# Sheet1.net
KiCad netlist of a schematic drawn in Altium Designer
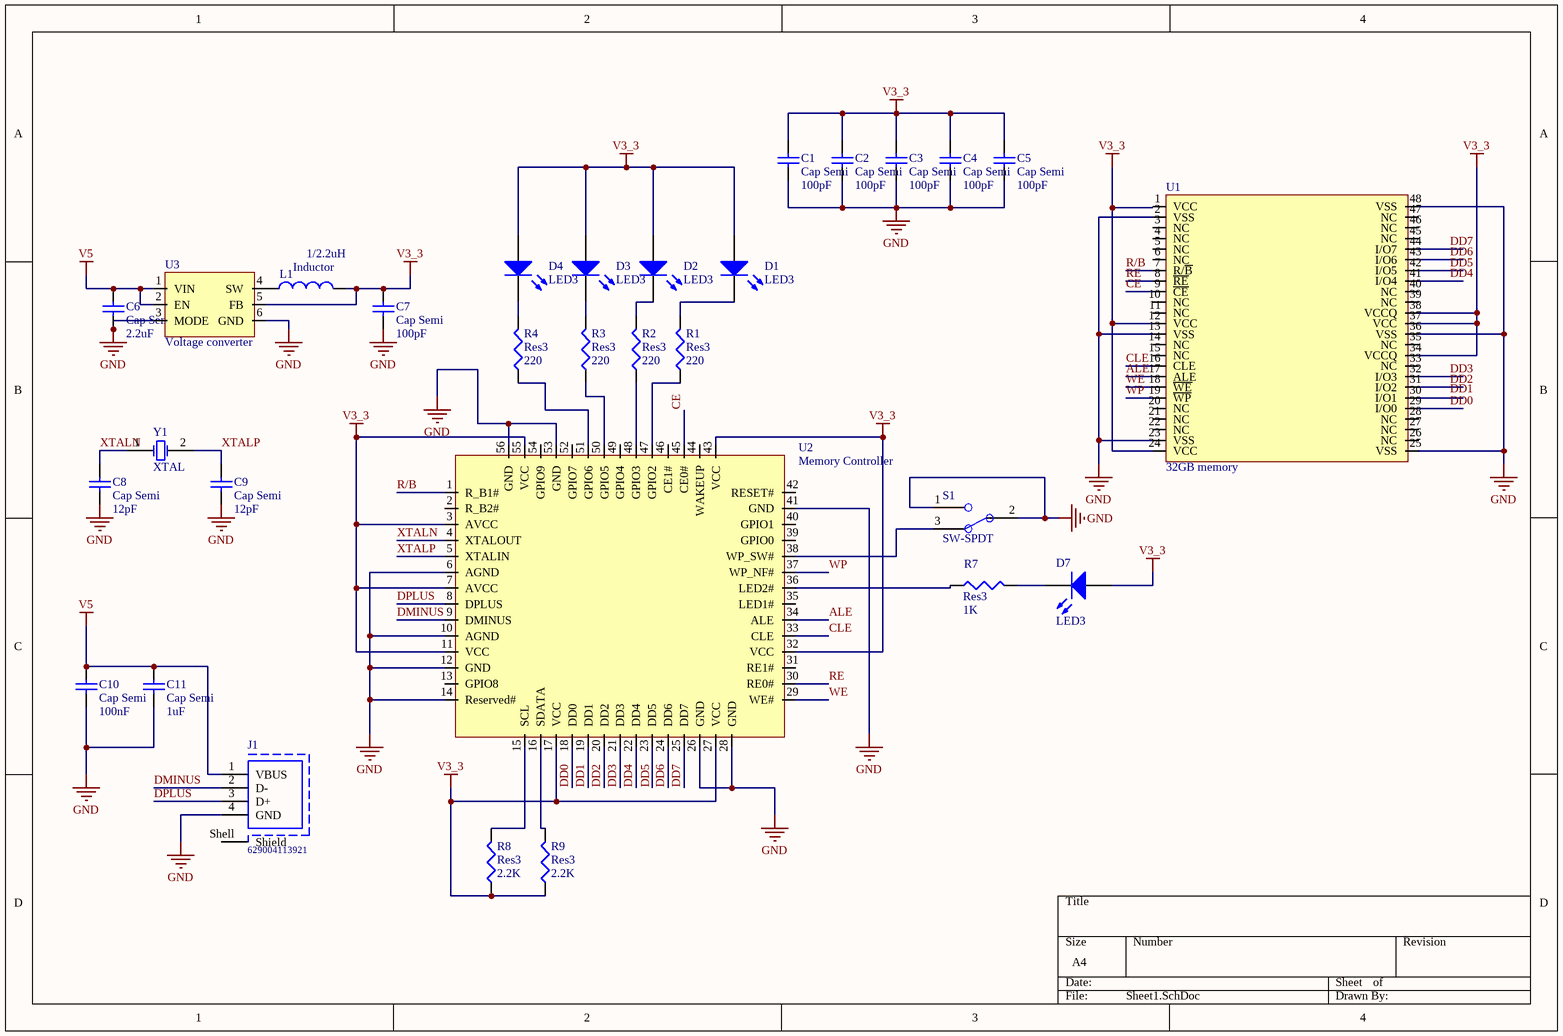
[diagram p0: Sheet1.SchDoc]

(export (version "E")
  (design (tool "Eeschema 10.0.6"))
  (components
    (comp (ref "C1")
      (value "Cap Semi")
      (footprint "CAPC3216L")
      (description "Capacitor (Semiconductor SIM Model)")
      (fields (field (name "ALTIUM_VALUE") "100pF") (field (name "PUBLISHER") "Altium Limited"))
      (libsource (lib "Miscellaneous Devices") (part "Cap Semi"))
    )
    (comp (ref "C2")
      (value "Cap Semi")
      (footprint "CAPC3216L")
      (description "Capacitor (Semiconductor SIM Model)")
      (fields (field (name "ALTIUM_VALUE") "100pF") (field (name "PUBLISHER") "Altium Limited"))
      (libsource (lib "Miscellaneous Devices") (part "Cap Semi"))
    )
    (comp (ref "C3")
      (value "Cap Semi")
      (footprint "CAPC3216L")
      (description "Capacitor (Semiconductor SIM Model)")
      (fields (field (name "ALTIUM_VALUE") "100pF") (field (name "PUBLISHER") "Altium Limited"))
      (libsource (lib "Miscellaneous Devices") (part "Cap Semi"))
    )
    (comp (ref "C4")
      (value "Cap Semi")
      (footprint "CAPC3216L")
      (description "Capacitor (Semiconductor SIM Model)")
      (fields (field (name "ALTIUM_VALUE") "100pF") (field (name "PUBLISHER") "Altium Limited"))
      (libsource (lib "Miscellaneous Devices") (part "Cap Semi"))
    )
    (comp (ref "C5")
      (value "Cap Semi")
      (footprint "CAPC3216L")
      (description "Capacitor (Semiconductor SIM Model)")
      (fields (field (name "ALTIUM_VALUE") "100pF") (field (name "PUBLISHER") "Altium Limited"))
      (libsource (lib "Miscellaneous Devices") (part "Cap Semi"))
    )
    (comp (ref "C6")
      (value "Cap Semi")
      (footprint "CAPC3216L")
      (description "Capacitor (Semiconductor SIM Model)")
      (fields (field (name "ALTIUM_VALUE") "2.2uF") (field (name "PUBLISHER") "Altium Limited"))
      (libsource (lib "Miscellaneous Devices") (part "Cap Semi"))
    )
    (comp (ref "C7")
      (value "Cap Semi")
      (footprint "CAPC3216L")
      (description "Capacitor (Semiconductor SIM Model)")
      (fields (field (name "ALTIUM_VALUE") "100pF") (field (name "PUBLISHER") "Altium Limited"))
      (libsource (lib "Miscellaneous Devices") (part "Cap Semi"))
    )
    (comp (ref "C8")
      (value "Cap Semi")
      (footprint "CAPC3216L")
      (description "Capacitor (Semiconductor SIM Model)")
      (fields (field (name "ALTIUM_VALUE") "12pF") (field (name "PUBLISHER") "Altium Limited"))
      (libsource (lib "Miscellaneous Devices") (part "Cap Semi"))
    )
    (comp (ref "C9")
      (value "Cap Semi")
      (footprint "CAPC3216L")
      (description "Capacitor (Semiconductor SIM Model)")
      (fields (field (name "ALTIUM_VALUE") "12pF") (field (name "PUBLISHER") "Altium Limited"))
      (libsource (lib "Miscellaneous Devices") (part "Cap Semi"))
    )
    (comp (ref "C10")
      (value "Cap Semi")
      (footprint "CAPC3216L")
      (description "Capacitor (Semiconductor SIM Model)")
      (fields (field (name "ALTIUM_VALUE") "100nF") (field (name "PUBLISHER") "Altium Limited"))
      (libsource (lib "Miscellaneous Devices") (part "Cap Semi"))
    )
    (comp (ref "C11")
      (value "Cap Semi")
      (footprint "CAPC3216L")
      (description "Capacitor (Semiconductor SIM Model)")
      (fields (field (name "ALTIUM_VALUE") "1uF") (field (name "PUBLISHER") "Altium Limited"))
      (libsource (lib "Miscellaneous Devices") (part "Cap Semi"))
    )
    (comp (ref "D1")
      (value "LED3")
      (footprint "DSO-C2/D5.6")
      (description "Typical BLUE SiC LED")
      (fields (field (name "PUBLISHER") "Altium Limited"))
      (libsource (lib "Miscellaneous Devices") (part "LED3"))
    )
    (comp (ref "D2")
      (value "LED3")
      (footprint "DSO-C2/D5.6")
      (description "Typical BLUE SiC LED")
      (fields (field (name "PUBLISHER") "Altium Limited"))
      (libsource (lib "Miscellaneous Devices") (part "LED3"))
    )
    (comp (ref "D3")
      (value "LED3")
      (footprint "DSO-C2/D5.6")
      (description "Typical BLUE SiC LED")
      (fields (field (name "PUBLISHER") "Altium Limited"))
      (libsource (lib "Miscellaneous Devices") (part "LED3"))
    )
    (comp (ref "D4")
      (value "LED3")
      (footprint "DSO-C2/D5.6")
      (description "Typical BLUE SiC LED")
      (fields (field (name "PUBLISHER") "Altium Limited"))
      (libsource (lib "Miscellaneous Devices") (part "LED3"))
    )
    (comp (ref "D7")
      (value "LED3")
      (footprint "DSO-C2/D5.6")
      (description "Typical BLUE SiC LED")
      (fields (field (name "PUBLISHER") "Altium Limited"))
      (libsource (lib "Miscellaneous Devices") (part "LED3"))
    )
    (comp (ref "J1")
      (value "629004113921")
      (footprint "629004113921")
      (description "USB 2.0 Type A Plug WR-COM, Horizontal, SMT, with Clips")
      (fields (field (name "PUBLISHER") "Wurth Elektronik"))
      (libsource (lib "Altium_WR-COM_USB-Connectors (rev19a)") (part "629004113921"))
    )
    (comp (ref "L1")
      (value "Inductor")
      (footprint "INDC1005AL")
      (fields (field (name "ALTIUM_VALUE") "1/2.2uH") (field (name "PUBLISHER") "Altium Limited"))
      (libsource (lib "Miscellaneous Devices") (part "Inductor"))
    )
    (comp (ref "R1")
      (value "Res3")
      (footprint "RESC1608L")
      (description "Resistor")
      (fields (field (name "ALTIUM_VALUE") "220") (field (name "PUBLISHER") "Altium Limited"))
      (libsource (lib "Miscellaneous Devices") (part "Res3"))
    )
    (comp (ref "R2")
      (value "Res3")
      (footprint "RESC1608L")
      (description "Resistor")
      (fields (field (name "ALTIUM_VALUE") "220") (field (name "PUBLISHER") "Altium Limited"))
      (libsource (lib "Miscellaneous Devices") (part "Res3"))
    )
    (comp (ref "R3")
      (value "Res3")
      (footprint "RESC1608L")
      (description "Resistor")
      (fields (field (name "ALTIUM_VALUE") "220") (field (name "PUBLISHER") "Altium Limited"))
      (libsource (lib "Miscellaneous Devices") (part "Res3"))
    )
    (comp (ref "R4")
      (value "Res3")
      (footprint "RESC1608L")
      (description "Resistor")
      (fields (field (name "ALTIUM_VALUE") "220") (field (name "PUBLISHER") "Altium Limited"))
      (libsource (lib "Miscellaneous Devices") (part "Res3"))
    )
    (comp (ref "R7")
      (value "Res3")
      (footprint "RESC1608L")
      (description "Resistor")
      (fields (field (name "ALTIUM_VALUE") "1K") (field (name "PUBLISHER") "Altium Limited"))
      (libsource (lib "Miscellaneous Devices") (part "Res3"))
    )
    (comp (ref "R8")
      (value "Res3")
      (footprint "RESC1608L")
      (description "Resistor")
      (fields (field (name "ALTIUM_VALUE") "2.2K") (field (name "PUBLISHER") "Altium Limited"))
      (libsource (lib "Miscellaneous Devices") (part "Res3"))
    )
    (comp (ref "R9")
      (value "Res3")
      (footprint "RESC1608L")
      (description "Resistor")
      (fields (field (name "ALTIUM_VALUE") "2.2K") (field (name "PUBLISHER") "Altium Limited"))
      (libsource (lib "Miscellaneous Devices") (part "Res3"))
    )
    (comp (ref "S1")
      (value "SW-SPDT")
      (footprint "SW-SPDT")
      (libsource (lib "Integrated_Library1") (part "Component_4"))
    )
    (comp (ref "U1")
      (value "32GB memory")
      (footprint "TSSOP50P2000X120-48N")
      (libsource (lib "Integrated_Library1") (part "Component_2"))
    )
    (comp (ref "U2")
      (value "Memory Controller")
      (footprint "QFN50P800X800X100-56N")
      (libsource (lib "Integrated_Library1") (part "Component_1"))
    )
    (comp (ref "U3")
      (value "Voltage converter")
      (footprint "USON")
      (libsource (lib "Integrated_Library1") (part "Component_3"))
    )
    (comp (ref "Y1")
      (value "XTAL")
      (footprint "BCY-W2/D3.1")
      (description "Crystal Oscillator")
      (fields (field (name "PUBLISHER") "Altium Limited"))
      (libsource (lib "Miscellaneous Devices") (part "XTAL"))
    )
  )
  (nets
    (net (code "1") (name "/ALE") (class "Default")
      (node (ref "U1") (pin "17") (pinfunction "ALE_17") (pintype "passive"))
      (node (ref "U2") (pin "34") (pinfunction "ALE_34") (pintype "passive"))
    )
    (net (code "2") (name "/CE") (class "Default")
      (node (ref "U1") (pin "9") (pinfunction "~{CE}_9") (pintype "passive"))
      (node (ref "U2") (pin "45") (pinfunction "CE0#_45") (pintype "passive"))
    )
    (net (code "3") (name "/CLE") (class "Default")
      (node (ref "U1") (pin "16") (pinfunction "CLE_16") (pintype "passive"))
      (node (ref "U2") (pin "33") (pinfunction "CLE_33") (pintype "passive"))
    )
    (net (code "4") (name "/DD0") (class "Default")
      (node (ref "U1") (pin "29") (pinfunction "I/O0_29") (pintype "passive"))
      (node (ref "U2") (pin "18") (pinfunction "DD0_18") (pintype "passive"))
    )
    (net (code "5") (name "/DD1") (class "Default")
      (node (ref "U2") (pin "19") (pinfunction "DD1_19") (pintype "passive"))
    )
    (net (code "6") (name "/DD2") (class "Default")
      (node (ref "U1") (pin "31") (pinfunction "I/O2_31") (pintype "passive"))
      (node (ref "U2") (pin "20") (pinfunction "DD2_20") (pintype "passive"))
    )
    (net (code "7") (name "/DD3") (class "Default")
      (node (ref "U1") (pin "32") (pinfunction "I/O3_32") (pintype "passive"))
      (node (ref "U2") (pin "21") (pinfunction "DD3_21") (pintype "passive"))
    )
    (net (code "8") (name "/DD4") (class "Default")
      (node (ref "U1") (pin "41") (pinfunction "I/O4_41") (pintype "passive"))
      (node (ref "U2") (pin "22") (pinfunction "DD4_22") (pintype "passive"))
    )
    (net (code "9") (name "/DD5") (class "Default")
      (node (ref "U1") (pin "42") (pinfunction "I/O5_42") (pintype "passive"))
    )
    (net (code "10") (name "/DD6") (class "Default")
      (node (ref "U1") (pin "43") (pinfunction "I/O6_43") (pintype "passive"))
      (node (ref "U2") (pin "24") (pinfunction "DD6_24") (pintype "passive"))
    )
    (net (code "11") (name "/DD7") (class "Default")
      (node (ref "U1") (pin "44") (pinfunction "I/O7_44") (pintype "passive"))
      (node (ref "U2") (pin "25") (pinfunction "DD7_25") (pintype "passive"))
    )
    (net (code "12") (name "/DMINUS") (class "Default")
      (node (ref "J1") (pin "2") (pinfunction "D-_2") (pintype "passive"))
      (node (ref "U2") (pin "9") (pinfunction "DMINUS_9") (pintype "passive"))
    )
    (net (code "13") (name "/DPLUS") (class "Default")
      (node (ref "J1") (pin "3") (pinfunction "D+_3") (pintype "passive"))
      (node (ref "U2") (pin "8") (pinfunction "DPLUS_8") (pintype "passive"))
    )
    (net (code "14") (name "/RE") (class "Default")
      (node (ref "U1") (pin "8") (pinfunction "~{RE}_8") (pintype "passive"))
      (node (ref "U2") (pin "30") (pinfunction "RE0#_30") (pintype "passive"))
    )
    (net (code "15") (name "/R{slash}B") (class "Default")
      (node (ref "U1") (pin "7") (pinfunction "R/~{B}_7") (pintype "passive"))
      (node (ref "U2") (pin "1") (pinfunction "R_B1#_1") (pintype "passive"))
    )
    (net (code "16") (name "/WE") (class "Default")
      (node (ref "U1") (pin "18") (pinfunction "~{WE}_18") (pintype "passive"))
      (node (ref "U2") (pin "29") (pinfunction "WE#_29") (pintype "passive"))
    )
    (net (code "17") (name "/WP") (class "Default")
      (node (ref "U1") (pin "19") (pinfunction "~{WP}_19") (pintype "passive"))
      (node (ref "U2") (pin "37") (pinfunction "WP_NF#_37") (pintype "passive"))
    )
    (net (code "18") (name "/XTALN") (class "Default")
      (node (ref "C8") (pin "2") (pinfunction "2_2") (pintype "passive"))
      (node (ref "U2") (pin "4") (pinfunction "XTALOUT_4") (pintype "passive"))
      (node (ref "Y1") (pin "1") (pinfunction "OSC1_1") (pintype "passive"))
    )
    (net (code "19") (name "/XTALP") (class "Default")
      (node (ref "C9") (pin "2") (pinfunction "2_2") (pintype "passive"))
      (node (ref "U2") (pin "5") (pinfunction "XTALIN_5") (pintype "passive"))
      (node (ref "Y1") (pin "2") (pinfunction "OSC2_2") (pintype "passive"))
    )
    (net (code "20") (name "GND") (class "Default")
      (node (ref "C1") (pin "1") (pinfunction "1_1") (pintype "passive"))
      (node (ref "C10") (pin "1") (pinfunction "1_1") (pintype "passive"))
      (node (ref "C11") (pin "1") (pinfunction "1_1") (pintype "passive"))
      (node (ref "C2") (pin "1") (pinfunction "1_1") (pintype "passive"))
      (node (ref "C3") (pin "1") (pinfunction "1_1") (pintype "passive"))
      (node (ref "C4") (pin "1") (pinfunction "1_1") (pintype "passive"))
      (node (ref "C5") (pin "1") (pinfunction "1_1") (pintype "passive"))
      (node (ref "C6") (pin "2") (pinfunction "2_2") (pintype "passive"))
      (node (ref "C7") (pin "1") (pinfunction "1_1") (pintype "passive"))
      (node (ref "C8") (pin "1") (pinfunction "1_1") (pintype "passive"))
      (node (ref "C9") (pin "1") (pinfunction "1_1") (pintype "passive"))
      (node (ref "J1") (pin "4") (pinfunction "GND_4") (pintype "passive"))
      (node (ref "S1") (pin "1") (pinfunction "1_1") (pintype "passive"))
      (node (ref "S1") (pin "2") (pinfunction "2_2") (pintype "passive"))
      (node (ref "U1") (pin "13") (pinfunction "VSS_13") (pintype "passive"))
      (node (ref "U1") (pin "2") (pinfunction "VSS_2") (pintype "passive"))
      (node (ref "U1") (pin "23") (pinfunction "VSS_23") (pintype "passive"))
      (node (ref "U1") (pin "25") (pinfunction "VSS_25") (pintype "passive"))
      (node (ref "U1") (pin "36") (pinfunction "VSS_36") (pintype "passive"))
      (node (ref "U1") (pin "48") (pinfunction "VSS_48") (pintype "passive"))
      (node (ref "U2") (pin "10") (pinfunction "AGND_10") (pintype "passive"))
      (node (ref "U2") (pin "12") (pinfunction "GND_12") (pintype "passive"))
      (node (ref "U2") (pin "14") (pinfunction "Reserved#_14") (pintype "passive"))
      (node (ref "U2") (pin "26") (pinfunction "GND_26") (pintype "passive"))
      (node (ref "U2") (pin "28") (pinfunction "GND_28") (pintype "passive"))
      (node (ref "U2") (pin "41") (pinfunction "GND_41") (pintype "passive"))
      (node (ref "U2") (pin "53") (pinfunction "GND_53") (pintype "passive"))
      (node (ref "U2") (pin "56") (pinfunction "GND_56") (pintype "passive"))
      (node (ref "U2") (pin "6") (pinfunction "AGND_6") (pintype "passive"))
      (node (ref "U3") (pin "3") (pinfunction "MODE_3") (pintype "passive"))
      (node (ref "U3") (pin "6") (pinfunction "GND_6") (pintype "passive"))
    )
    (net (code "21") (name "Net-(D1-K)") (class "Default")
      (node (ref "D1") (pin "2") (pinfunction "K_2") (pintype "passive"))
      (node (ref "R1") (pin "2") (pinfunction "2_2") (pintype "passive"))
    )
    (net (code "22") (name "Net-(D2-K)") (class "Default")
      (node (ref "D2") (pin "2") (pinfunction "K_2") (pintype "passive"))
      (node (ref "R2") (pin "2") (pinfunction "2_2") (pintype "passive"))
    )
    (net (code "23") (name "Net-(D3-K)") (class "Default")
      (node (ref "D3") (pin "2") (pinfunction "K_2") (pintype "passive"))
      (node (ref "R3") (pin "2") (pinfunction "2_2") (pintype "passive"))
    )
    (net (code "24") (name "Net-(D4-K)") (class "Default")
      (node (ref "D4") (pin "2") (pinfunction "K_2") (pintype "passive"))
      (node (ref "R4") (pin "2") (pinfunction "2_2") (pintype "passive"))
    )
    (net (code "25") (name "Net-(D7-K)") (class "Default")
      (node (ref "D7") (pin "2") (pinfunction "K_2") (pintype "passive"))
      (node (ref "R7") (pin "2") (pinfunction "2_2") (pintype "passive"))
    )
    (net (code "26") (name "Net-(U2-GPIO2)") (class "Default")
      (node (ref "R1") (pin "1") (pinfunction "1_1") (pintype "passive"))
      (node (ref "U2") (pin "47") (pinfunction "GPIO2_47") (pintype "passive"))
    )
    (net (code "27") (name "Net-(U2-GPIO3)") (class "Default")
      (node (ref "R2") (pin "1") (pinfunction "1_1") (pintype "passive"))
      (node (ref "U2") (pin "48") (pinfunction "GPIO3_48") (pintype "passive"))
    )
    (net (code "28") (name "Net-(U2-GPIO5)") (class "Default")
      (node (ref "R3") (pin "1") (pinfunction "1_1") (pintype "passive"))
      (node (ref "U2") (pin "50") (pinfunction "GPIO5_50") (pintype "passive"))
    )
    (net (code "29") (name "Net-(U2-GPIO6)") (class "Default")
      (node (ref "R4") (pin "1") (pinfunction "1_1") (pintype "passive"))
      (node (ref "U2") (pin "51") (pinfunction "GPIO6_51") (pintype "passive"))
    )
    (net (code "30") (name "Net-(U2-LED2#)") (class "Default")
      (node (ref "R7") (pin "1") (pinfunction "1_1") (pintype "passive"))
      (node (ref "U2") (pin "36") (pinfunction "LED2#_36") (pintype "passive"))
    )
    (net (code "31") (name "Net-(U2-SCL)") (class "Default")
      (node (ref "R8") (pin "2") (pinfunction "2_2") (pintype "passive"))
      (node (ref "U2") (pin "15") (pinfunction "SCL_15") (pintype "passive"))
    )
    (net (code "32") (name "Net-(U2-SDATA)") (class "Default")
      (node (ref "R9") (pin "2") (pinfunction "2_2") (pintype "passive"))
      (node (ref "U2") (pin "16") (pinfunction "SDATA_16") (pintype "passive"))
    )
    (net (code "33") (name "Net-(U2-WP_SW#)") (class "Default")
      (node (ref "S1") (pin "3") (pinfunction "3_3") (pintype "passive"))
      (node (ref "U2") (pin "38") (pinfunction "WP_SW#_38") (pintype "passive"))
    )
    (net (code "34") (name "Net-(U3-SW)") (class "Default")
      (node (ref "L1") (pin "1") (pinfunction "1_1") (pintype "passive"))
      (node (ref "U3") (pin "4") (pinfunction "SW_4") (pintype "passive"))
    )
    (net (code "35") (name "V3_3") (class "Default")
      (node (ref "C1") (pin "2") (pinfunction "2_2") (pintype "passive"))
      (node (ref "C2") (pin "2") (pinfunction "2_2") (pintype "passive"))
      (node (ref "C3") (pin "2") (pinfunction "2_2") (pintype "passive"))
      (node (ref "C4") (pin "2") (pinfunction "2_2") (pintype "passive"))
      (node (ref "C5") (pin "2") (pinfunction "2_2") (pintype "passive"))
      (node (ref "C7") (pin "2") (pinfunction "2_2") (pintype "passive"))
      (node (ref "D1") (pin "1") (pinfunction "A_1") (pintype "passive"))
      (node (ref "D2") (pin "1") (pinfunction "A_1") (pintype "passive"))
      (node (ref "D3") (pin "1") (pinfunction "A_1") (pintype "passive"))
      (node (ref "D4") (pin "1") (pinfunction "A_1") (pintype "passive"))
      (node (ref "D7") (pin "1") (pinfunction "A_1") (pintype "passive"))
      (node (ref "L1") (pin "2") (pinfunction "2_2") (pintype "passive"))
      (node (ref "R8") (pin "1") (pinfunction "1_1") (pintype "passive"))
      (node (ref "R9") (pin "1") (pinfunction "1_1") (pintype "passive"))
      (node (ref "U1") (pin "12") (pinfunction "VCC_12") (pintype "passive"))
      (node (ref "U1") (pin "24") (pinfunction "VCC_24") (pintype "passive"))
      (node (ref "U1") (pin "34") (pinfunction "VCCQ_34") (pintype "passive"))
      (node (ref "U1") (pin "37") (pinfunction "VCC_37") (pintype "passive"))
      (node (ref "U1") (pin "38") (pinfunction "VCCQ_38") (pintype "passive"))
      (node (ref "U2") (pin "11") (pinfunction "VCC_11") (pintype "passive"))
      (node (ref "U2") (pin "17") (pinfunction "VCC_17") (pintype "passive"))
      (node (ref "U2") (pin "27") (pinfunction "VCC_27") (pintype "passive"))
      (node (ref "U2") (pin "3") (pinfunction "AVCC_3") (pintype "passive"))
      (node (ref "U2") (pin "32") (pinfunction "VCC_32") (pintype "passive"))
      (node (ref "U2") (pin "43") (pinfunction "VCC_43") (pintype "passive"))
      (node (ref "U2") (pin "55") (pinfunction "VCC_55") (pintype "passive"))
      (node (ref "U2") (pin "7") (pinfunction "AVCC_7") (pintype "passive"))
      (node (ref "U3") (pin "5") (pinfunction "FB_5") (pintype "passive"))
    )
    (net (code "36") (name "V5") (class "Default")
      (node (ref "C10") (pin "2") (pinfunction "2_2") (pintype "passive"))
      (node (ref "C11") (pin "2") (pinfunction "2_2") (pintype "passive"))
      (node (ref "C6") (pin "1") (pinfunction "1_1") (pintype "passive"))
      (node (ref "J1") (pin "1") (pinfunction "VBUS_1") (pintype "passive"))
      (node (ref "U3") (pin "1") (pinfunction "VIN_1") (pintype "passive"))
      (node (ref "U3") (pin "2") (pinfunction "EN_2") (pintype "passive"))
    )
    (net (code "37") (name "unconnected-(J1-Shield-PadShell)") (class "Default")
      (node (ref "J1") (pin "Shell") (pinfunction "Shield_Shell") (pintype "passive"))
    )
    (net (code "38") (name "unconnected-(U1-I{slash}O1-Pad30)") (class "Default")
      (node (ref "U1") (pin "30") (pinfunction "I/O1_30") (pintype "passive"))
    )
    (net (code "39") (name "unconnected-(U1-NC-Pad3)") (class "Default")
      (node (ref "U1") (pin "3") (pinfunction "NC_3") (pintype "passive"))
    )
    (net (code "40") (name "unconnected-(U1-NC-Pad4)") (class "Default")
      (node (ref "U1") (pin "4") (pinfunction "NC_4") (pintype "passive"))
    )
    (net (code "41") (name "unconnected-(U1-NC-Pad5)") (class "Default")
      (node (ref "U1") (pin "5") (pinfunction "NC_5") (pintype "passive"))
    )
    (net (code "42") (name "unconnected-(U1-NC-Pad6)") (class "Default")
      (node (ref "U1") (pin "6") (pinfunction "NC_6") (pintype "passive"))
    )
    (net (code "43") (name "unconnected-(U1-NC-Pad10)") (class "Default")
      (node (ref "U1") (pin "10") (pinfunction "NC_10") (pintype "passive"))
    )
    (net (code "44") (name "unconnected-(U1-NC-Pad11)") (class "Default")
      (node (ref "U1") (pin "11") (pinfunction "NC_11") (pintype "passive"))
    )
    (net (code "45") (name "unconnected-(U1-NC-Pad14)") (class "Default")
      (node (ref "U1") (pin "14") (pinfunction "NC_14") (pintype "passive"))
    )
    (net (code "46") (name "unconnected-(U1-NC-Pad15)") (class "Default")
      (node (ref "U1") (pin "15") (pinfunction "NC_15") (pintype "passive"))
    )
    (net (code "47") (name "unconnected-(U1-NC-Pad20)") (class "Default")
      (node (ref "U1") (pin "20") (pinfunction "NC_20") (pintype "passive"))
    )
    (net (code "48") (name "unconnected-(U1-NC-Pad21)") (class "Default")
      (node (ref "U1") (pin "21") (pinfunction "NC_21") (pintype "passive"))
    )
    (net (code "49") (name "unconnected-(U1-NC-Pad22)") (class "Default")
      (node (ref "U1") (pin "22") (pinfunction "NC_22") (pintype "passive"))
    )
    (net (code "50") (name "unconnected-(U1-NC-Pad26)") (class "Default")
      (node (ref "U1") (pin "26") (pinfunction "NC_26") (pintype "passive"))
    )
    (net (code "51") (name "unconnected-(U1-NC-Pad27)") (class "Default")
      (node (ref "U1") (pin "27") (pinfunction "NC_27") (pintype "passive"))
    )
    (net (code "52") (name "unconnected-(U1-NC-Pad28)") (class "Default")
      (node (ref "U1") (pin "28") (pinfunction "NC_28") (pintype "passive"))
    )
    (net (code "53") (name "unconnected-(U1-NC-Pad33)") (class "Default")
      (node (ref "U1") (pin "33") (pinfunction "NC_33") (pintype "passive"))
    )
    (net (code "54") (name "unconnected-(U1-NC-Pad35)") (class "Default")
      (node (ref "U1") (pin "35") (pinfunction "NC_35") (pintype "passive"))
    )
    (net (code "55") (name "unconnected-(U1-NC-Pad39)") (class "Default")
      (node (ref "U1") (pin "39") (pinfunction "NC_39") (pintype "passive"))
    )
    (net (code "56") (name "unconnected-(U1-NC-Pad40)") (class "Default")
      (node (ref "U1") (pin "40") (pinfunction "NC_40") (pintype "passive"))
    )
    (net (code "57") (name "unconnected-(U1-NC-Pad45)") (class "Default")
      (node (ref "U1") (pin "45") (pinfunction "NC_45") (pintype "passive"))
    )
    (net (code "58") (name "unconnected-(U1-NC-Pad46)") (class "Default")
      (node (ref "U1") (pin "46") (pinfunction "NC_46") (pintype "passive"))
    )
    (net (code "59") (name "unconnected-(U1-NC-Pad47)") (class "Default")
      (node (ref "U1") (pin "47") (pinfunction "NC_47") (pintype "passive"))
    )
    (net (code "60") (name "unconnected-(U1-VCC-Pad1)") (class "Default")
      (node (ref "U1") (pin "1") (pinfunction "VCC_1") (pintype "passive"))
    )
    (net (code "61") (name "unconnected-(U2-CE1#-Pad46)") (class "Default")
      (node (ref "U2") (pin "46") (pinfunction "CE1#_46") (pintype "passive"))
    )
    (net (code "62") (name "unconnected-(U2-DD5-Pad23)") (class "Default")
      (node (ref "U2") (pin "23") (pinfunction "DD5_23") (pintype "passive"))
    )
    (net (code "63") (name "unconnected-(U2-GPIO0-Pad39)") (class "Default")
      (node (ref "U2") (pin "39") (pinfunction "GPIO0_39") (pintype "passive"))
    )
    (net (code "64") (name "unconnected-(U2-GPIO1-Pad40)") (class "Default")
      (node (ref "U2") (pin "40") (pinfunction "GPIO1_40") (pintype "passive"))
    )
    (net (code "65") (name "unconnected-(U2-GPIO4-Pad49)") (class "Default")
      (node (ref "U2") (pin "49") (pinfunction "GPIO4_49") (pintype "passive"))
    )
    (net (code "66") (name "unconnected-(U2-GPIO7-Pad52)") (class "Default")
      (node (ref "U2") (pin "52") (pinfunction "GPIO7_52") (pintype "passive"))
    )
    (net (code "67") (name "unconnected-(U2-GPIO8-Pad13)") (class "Default")
      (node (ref "U2") (pin "13") (pinfunction "GPIO8_13") (pintype "passive"))
    )
    (net (code "68") (name "unconnected-(U2-GPIO9-Pad54)") (class "Default")
      (node (ref "U2") (pin "54") (pinfunction "GPIO9_54") (pintype "passive"))
    )
    (net (code "69") (name "unconnected-(U2-LED1#-Pad35)") (class "Default")
      (node (ref "U2") (pin "35") (pinfunction "LED1#_35") (pintype "passive"))
    )
    (net (code "70") (name "unconnected-(U2-RE1#-Pad31)") (class "Default")
      (node (ref "U2") (pin "31") (pinfunction "RE1#_31") (pintype "passive"))
    )
    (net (code "71") (name "unconnected-(U2-RESET#-Pad42)") (class "Default")
      (node (ref "U2") (pin "42") (pinfunction "RESET#_42") (pintype "passive"))
    )
    (net (code "72") (name "unconnected-(U2-R_B2#-Pad2)") (class "Default")
      (node (ref "U2") (pin "2") (pinfunction "R_B2#_2") (pintype "passive"))
    )
    (net (code "73") (name "unconnected-(U2-WAKEUP-Pad44)") (class "Default")
      (node (ref "U2") (pin "44") (pinfunction "WAKEUP_44") (pintype "passive"))
    )
  )
)
